# Switch_Decoderv06.net
KiCad netlist of a schematic drawn in EAGLE
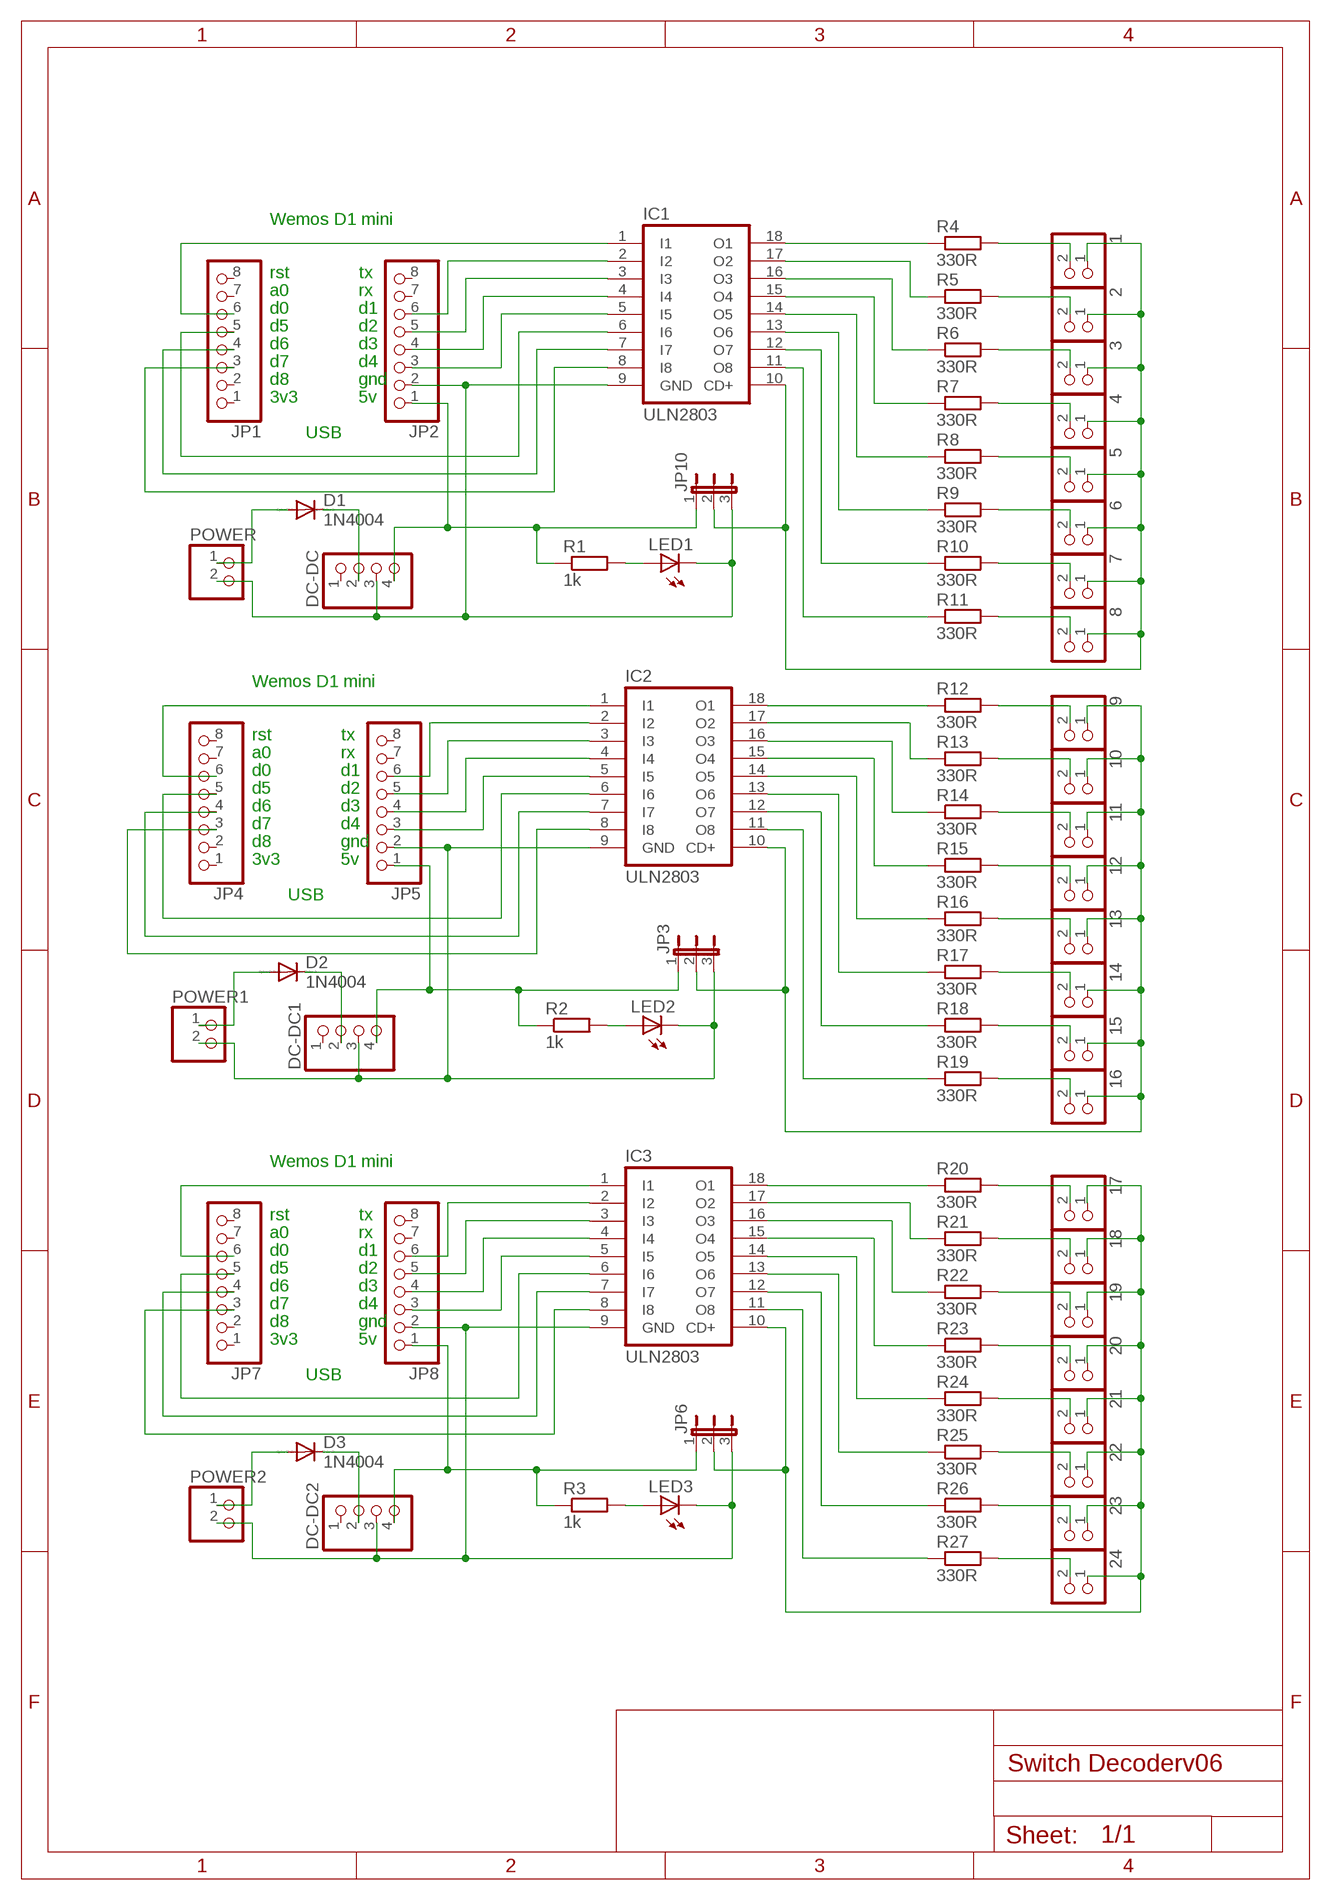
[diagram p0: schematic, sheet 1]

(export (version "E")
  (design (tool "Eeschema 10.0.6"))
  (components
    (comp (ref "1")
      (value "PINHD-1X2")
      (footprint "eagle-import:1X02")
      (libsource (lib "eagle-import") (part "PINHD-1X2"))
    )
    (comp (ref "2")
      (value "PINHD-1X2")
      (footprint "eagle-import:1X02")
      (libsource (lib "eagle-import") (part "PINHD-1X2"))
    )
    (comp (ref "3")
      (value "PINHD-1X2")
      (footprint "eagle-import:1X02")
      (libsource (lib "eagle-import") (part "PINHD-1X2"))
    )
    (comp (ref "4")
      (value "PINHD-1X2")
      (footprint "eagle-import:1X02")
      (libsource (lib "eagle-import") (part "PINHD-1X2"))
    )
    (comp (ref "5")
      (value "PINHD-1X2")
      (footprint "eagle-import:1X02")
      (libsource (lib "eagle-import") (part "PINHD-1X2"))
    )
    (comp (ref "6")
      (value "PINHD-1X2")
      (footprint "eagle-import:1X02")
      (libsource (lib "eagle-import") (part "PINHD-1X2"))
    )
    (comp (ref "7")
      (value "PINHD-1X2")
      (footprint "eagle-import:1X02")
      (libsource (lib "eagle-import") (part "PINHD-1X2"))
    )
    (comp (ref "8")
      (value "PINHD-1X2")
      (footprint "eagle-import:1X02")
      (libsource (lib "eagle-import") (part "PINHD-1X2"))
    )
    (comp (ref "9")
      (value "PINHD-1X2")
      (footprint "eagle-import:1X02")
      (libsource (lib "eagle-import") (part "PINHD-1X2"))
    )
    (comp (ref "10")
      (value "PINHD-1X2")
      (footprint "eagle-import:1X02")
      (libsource (lib "eagle-import") (part "PINHD-1X2"))
    )
    (comp (ref "11")
      (value "PINHD-1X2")
      (footprint "eagle-import:1X02")
      (libsource (lib "eagle-import") (part "PINHD-1X2"))
    )
    (comp (ref "12")
      (value "PINHD-1X2")
      (footprint "eagle-import:1X02")
      (libsource (lib "eagle-import") (part "PINHD-1X2"))
    )
    (comp (ref "13")
      (value "PINHD-1X2")
      (footprint "eagle-import:1X02")
      (libsource (lib "eagle-import") (part "PINHD-1X2"))
    )
    (comp (ref "14")
      (value "PINHD-1X2")
      (footprint "eagle-import:1X02")
      (libsource (lib "eagle-import") (part "PINHD-1X2"))
    )
    (comp (ref "15")
      (value "PINHD-1X2")
      (footprint "eagle-import:1X02")
      (libsource (lib "eagle-import") (part "PINHD-1X2"))
    )
    (comp (ref "16")
      (value "PINHD-1X2")
      (footprint "eagle-import:1X02")
      (libsource (lib "eagle-import") (part "PINHD-1X2"))
    )
    (comp (ref "17")
      (value "PINHD-1X2")
      (footprint "eagle-import:1X02")
      (libsource (lib "eagle-import") (part "PINHD-1X2"))
    )
    (comp (ref "18")
      (value "PINHD-1X2")
      (footprint "eagle-import:1X02")
      (libsource (lib "eagle-import") (part "PINHD-1X2"))
    )
    (comp (ref "19")
      (value "PINHD-1X2")
      (footprint "eagle-import:1X02")
      (libsource (lib "eagle-import") (part "PINHD-1X2"))
    )
    (comp (ref "20")
      (value "PINHD-1X2")
      (footprint "eagle-import:1X02")
      (libsource (lib "eagle-import") (part "PINHD-1X2"))
    )
    (comp (ref "21")
      (value "PINHD-1X2")
      (footprint "eagle-import:1X02")
      (libsource (lib "eagle-import") (part "PINHD-1X2"))
    )
    (comp (ref "22")
      (value "PINHD-1X2")
      (footprint "eagle-import:1X02")
      (libsource (lib "eagle-import") (part "PINHD-1X2"))
    )
    (comp (ref "23")
      (value "PINHD-1X2")
      (footprint "eagle-import:1X02")
      (libsource (lib "eagle-import") (part "PINHD-1X2"))
    )
    (comp (ref "24")
      (value "PINHD-1X2")
      (footprint "eagle-import:1X02")
      (libsource (lib "eagle-import") (part "PINHD-1X2"))
    )
    (comp (ref "D1")
      (value "1N4004")
      (footprint "eagle-import:DO41-10")
      (libsource (lib "eagle-import") (part "1N4004"))
    )
    (comp (ref "D2")
      (value "1N4004")
      (footprint "eagle-import:DO41-10")
      (libsource (lib "eagle-import") (part "1N4004"))
    )
    (comp (ref "D3")
      (value "1N4004")
      (footprint "eagle-import:DO41-10")
      (libsource (lib "eagle-import") (part "1N4004"))
    )
    (comp (ref "DC-DC")
      (value "PINHD-1X4")
      (footprint "eagle-import:1X04")
      (libsource (lib "eagle-import") (part "PINHD-1X4"))
    )
    (comp (ref "DC-DC1")
      (value "PINHD-1X4")
      (footprint "eagle-import:1X04")
      (libsource (lib "eagle-import") (part "PINHD-1X4"))
    )
    (comp (ref "DC-DC2")
      (value "PINHD-1X4")
      (footprint "eagle-import:1X04")
      (libsource (lib "eagle-import") (part "PINHD-1X4"))
    )
    (comp (ref "IC1")
      (value "ULN2803")
      (footprint "eagle-import:DIL18")
      (libsource (lib "eagle-import") (part "ULN2803A"))
    )
    (comp (ref "IC2")
      (value "ULN2803")
      (footprint "eagle-import:DIL18")
      (libsource (lib "eagle-import") (part "ULN2803A"))
    )
    (comp (ref "IC3")
      (value "ULN2803")
      (footprint "eagle-import:DIL18")
      (libsource (lib "eagle-import") (part "ULN2803A"))
    )
    (comp (ref "JP1")
      (value "PINHD-1X8")
      (footprint "eagle-import:1X08")
      (libsource (lib "eagle-import") (part "PINHD-1X8"))
    )
    (comp (ref "JP2")
      (value "PINHD-1X8")
      (footprint "eagle-import:1X08")
      (libsource (lib "eagle-import") (part "PINHD-1X8"))
    )
    (comp (ref "JP3")
      (value "JP2E")
      (footprint "eagle-import:JP2")
      (libsource (lib "eagle-import") (part "JP2E"))
    )
    (comp (ref "JP4")
      (value "PINHD-1X8")
      (footprint "eagle-import:1X08")
      (libsource (lib "eagle-import") (part "PINHD-1X8"))
    )
    (comp (ref "JP5")
      (value "PINHD-1X8")
      (footprint "eagle-import:1X08")
      (libsource (lib "eagle-import") (part "PINHD-1X8"))
    )
    (comp (ref "JP6")
      (value "JP2E")
      (footprint "eagle-import:JP2")
      (libsource (lib "eagle-import") (part "JP2E"))
    )
    (comp (ref "JP7")
      (value "PINHD-1X8")
      (footprint "eagle-import:1X08")
      (libsource (lib "eagle-import") (part "PINHD-1X8"))
    )
    (comp (ref "JP8")
      (value "PINHD-1X8")
      (footprint "eagle-import:1X08")
      (libsource (lib "eagle-import") (part "PINHD-1X8"))
    )
    (comp (ref "JP10")
      (value "JP2E")
      (footprint "eagle-import:JP2")
      (libsource (lib "eagle-import") (part "JP2E"))
    )
    (comp (ref "LED1")
      (value "LED3MM")
      (footprint "eagle-import:LED3MM")
      (libsource (lib "eagle-import") (part "LED3MM"))
    )
    (comp (ref "LED2")
      (value "LED3MM")
      (footprint "eagle-import:LED3MM")
      (libsource (lib "eagle-import") (part "LED3MM"))
    )
    (comp (ref "LED3")
      (value "LED3MM")
      (footprint "eagle-import:LED3MM")
      (libsource (lib "eagle-import") (part "LED3MM"))
    )
    (comp (ref "POWER")
      (value "PINHD-1X2")
      (footprint "eagle-import:1X02")
      (libsource (lib "eagle-import") (part "PINHD-1X2"))
    )
    (comp (ref "POWER1")
      (value "PINHD-1X2")
      (footprint "eagle-import:1X02")
      (libsource (lib "eagle-import") (part "PINHD-1X2"))
    )
    (comp (ref "POWER2")
      (value "PINHD-1X2")
      (footprint "eagle-import:1X02")
      (libsource (lib "eagle-import") (part "PINHD-1X2"))
    )
    (comp (ref "R1")
      (value "1k")
      (footprint "eagle-import:0309_10")
      (libsource (lib "eagle-import") (part "R-EU_0309/10"))
    )
    (comp (ref "R2")
      (value "1k")
      (footprint "eagle-import:0309_10")
      (libsource (lib "eagle-import") (part "R-EU_0309/10"))
    )
    (comp (ref "R3")
      (value "1k")
      (footprint "eagle-import:0309_10")
      (libsource (lib "eagle-import") (part "R-EU_0309/10"))
    )
    (comp (ref "R4")
      (value "330R")
      (footprint "eagle-import:0207_7")
      (libsource (lib "eagle-import") (part "resistor_348_R-EU_0207/7"))
    )
    (comp (ref "R5")
      (value "330R")
      (footprint "eagle-import:0207_7")
      (libsource (lib "eagle-import") (part "resistor_348_R-EU_0207/7"))
    )
    (comp (ref "R6")
      (value "330R")
      (footprint "eagle-import:0207_7")
      (libsource (lib "eagle-import") (part "resistor_348_R-EU_0207/7"))
    )
    (comp (ref "R7")
      (value "330R")
      (footprint "eagle-import:0207_7")
      (libsource (lib "eagle-import") (part "resistor_348_R-EU_0207/7"))
    )
    (comp (ref "R8")
      (value "330R")
      (footprint "eagle-import:0207_7")
      (libsource (lib "eagle-import") (part "resistor_348_R-EU_0207/7"))
    )
    (comp (ref "R9")
      (value "330R")
      (footprint "eagle-import:0207_7")
      (libsource (lib "eagle-import") (part "resistor_348_R-EU_0207/7"))
    )
    (comp (ref "R10")
      (value "330R")
      (footprint "eagle-import:0207_7")
      (libsource (lib "eagle-import") (part "resistor_348_R-EU_0207/7"))
    )
    (comp (ref "R11")
      (value "330R")
      (footprint "eagle-import:0207_7")
      (libsource (lib "eagle-import") (part "resistor_348_R-EU_0207/7"))
    )
    (comp (ref "R12")
      (value "330R")
      (footprint "eagle-import:0207_7")
      (libsource (lib "eagle-import") (part "resistor_348_R-EU_0207/7"))
    )
    (comp (ref "R13")
      (value "330R")
      (footprint "eagle-import:0207_7")
      (libsource (lib "eagle-import") (part "resistor_348_R-EU_0207/7"))
    )
    (comp (ref "R14")
      (value "330R")
      (footprint "eagle-import:0207_7")
      (libsource (lib "eagle-import") (part "resistor_348_R-EU_0207/7"))
    )
    (comp (ref "R15")
      (value "330R")
      (footprint "eagle-import:0207_7")
      (libsource (lib "eagle-import") (part "resistor_348_R-EU_0207/7"))
    )
    (comp (ref "R16")
      (value "330R")
      (footprint "eagle-import:0207_7")
      (libsource (lib "eagle-import") (part "resistor_348_R-EU_0207/7"))
    )
    (comp (ref "R17")
      (value "330R")
      (footprint "eagle-import:0207_7")
      (libsource (lib "eagle-import") (part "resistor_348_R-EU_0207/7"))
    )
    (comp (ref "R18")
      (value "330R")
      (footprint "eagle-import:0207_7")
      (libsource (lib "eagle-import") (part "resistor_348_R-EU_0207/7"))
    )
    (comp (ref "R19")
      (value "330R")
      (footprint "eagle-import:0207_7")
      (libsource (lib "eagle-import") (part "resistor_348_R-EU_0207/7"))
    )
    (comp (ref "R20")
      (value "330R")
      (footprint "eagle-import:0207_7")
      (libsource (lib "eagle-import") (part "resistor_348_R-EU_0207/7"))
    )
    (comp (ref "R21")
      (value "330R")
      (footprint "eagle-import:0207_7")
      (libsource (lib "eagle-import") (part "resistor_348_R-EU_0207/7"))
    )
    (comp (ref "R22")
      (value "330R")
      (footprint "eagle-import:0207_7")
      (libsource (lib "eagle-import") (part "resistor_348_R-EU_0207/7"))
    )
    (comp (ref "R23")
      (value "330R")
      (footprint "eagle-import:0207_7")
      (libsource (lib "eagle-import") (part "resistor_348_R-EU_0207/7"))
    )
    (comp (ref "R24")
      (value "330R")
      (footprint "eagle-import:0207_7")
      (libsource (lib "eagle-import") (part "resistor_348_R-EU_0207/7"))
    )
    (comp (ref "R25")
      (value "330R")
      (footprint "eagle-import:0207_7")
      (libsource (lib "eagle-import") (part "resistor_348_R-EU_0207/7"))
    )
    (comp (ref "R26")
      (value "330R")
      (footprint "eagle-import:0207_7")
      (libsource (lib "eagle-import") (part "resistor_348_R-EU_0207/7"))
    )
    (comp (ref "R27")
      (value "330R")
      (footprint "eagle-import:0207_7")
      (libsource (lib "eagle-import") (part "resistor_348_R-EU_0207/7"))
    )
  )
  (nets
    (net (code "1") (name "Net-(1-Pad2)") (class "Default")
      (node (ref "1") (pin "2") (pinfunction "2_2") (pintype "passive"))
      (node (ref "R4") (pin "2") (pinfunction "2_2") (pintype "passive"))
    )
    (net (code "2") (name "Net-(2-Pad2)") (class "Default")
      (node (ref "2") (pin "2") (pinfunction "2_2") (pintype "passive"))
      (node (ref "R5") (pin "2") (pinfunction "2_2") (pintype "passive"))
    )
    (net (code "3") (name "Net-(3-Pad2)") (class "Default")
      (node (ref "3") (pin "2") (pinfunction "2_2") (pintype "passive"))
      (node (ref "R6") (pin "2") (pinfunction "2_2") (pintype "passive"))
    )
    (net (code "4") (name "Net-(4-Pad2)") (class "Default")
      (node (ref "4") (pin "2") (pinfunction "2_2") (pintype "passive"))
      (node (ref "R7") (pin "2") (pinfunction "2_2") (pintype "passive"))
    )
    (net (code "5") (name "Net-(5-Pad2)") (class "Default")
      (node (ref "5") (pin "2") (pinfunction "2_2") (pintype "passive"))
      (node (ref "R8") (pin "2") (pinfunction "2_2") (pintype "passive"))
    )
    (net (code "6") (name "Net-(6-Pad2)") (class "Default")
      (node (ref "6") (pin "2") (pinfunction "2_2") (pintype "passive"))
      (node (ref "R9") (pin "2") (pinfunction "2_2") (pintype "passive"))
    )
    (net (code "7") (name "Net-(7-Pad2)") (class "Default")
      (node (ref "7") (pin "2") (pinfunction "2_2") (pintype "passive"))
      (node (ref "R10") (pin "2") (pinfunction "2_2") (pintype "passive"))
    )
    (net (code "8") (name "Net-(8-Pad2)") (class "Default")
      (node (ref "8") (pin "2") (pinfunction "2_2") (pintype "passive"))
      (node (ref "R11") (pin "2") (pinfunction "2_2") (pintype "passive"))
    )
    (net (code "9") (name "Net-(9-Pad2)") (class "Default")
      (node (ref "9") (pin "2") (pinfunction "2_2") (pintype "passive"))
      (node (ref "R12") (pin "2") (pinfunction "2_2") (pintype "passive"))
    )
    (net (code "10") (name "Net-(10-Pad2)") (class "Default")
      (node (ref "10") (pin "2") (pinfunction "2_2") (pintype "passive"))
      (node (ref "R13") (pin "2") (pinfunction "2_2") (pintype "passive"))
    )
    (net (code "11") (name "Net-(11-Pad2)") (class "Default")
      (node (ref "11") (pin "2") (pinfunction "2_2") (pintype "passive"))
      (node (ref "R14") (pin "2") (pinfunction "2_2") (pintype "passive"))
    )
    (net (code "12") (name "Net-(12-Pad2)") (class "Default")
      (node (ref "12") (pin "2") (pinfunction "2_2") (pintype "passive"))
      (node (ref "R15") (pin "2") (pinfunction "2_2") (pintype "passive"))
    )
    (net (code "13") (name "Net-(13-Pad2)") (class "Default")
      (node (ref "13") (pin "2") (pinfunction "2_2") (pintype "passive"))
      (node (ref "R16") (pin "2") (pinfunction "2_2") (pintype "passive"))
    )
    (net (code "14") (name "Net-(14-Pad2)") (class "Default")
      (node (ref "14") (pin "2") (pinfunction "2_2") (pintype "passive"))
      (node (ref "R17") (pin "2") (pinfunction "2_2") (pintype "passive"))
    )
    (net (code "15") (name "Net-(15-Pad2)") (class "Default")
      (node (ref "15") (pin "2") (pinfunction "2_2") (pintype "passive"))
      (node (ref "R18") (pin "2") (pinfunction "2_2") (pintype "passive"))
    )
    (net (code "16") (name "Net-(16-Pad2)") (class "Default")
      (node (ref "16") (pin "2") (pinfunction "2_2") (pintype "passive"))
      (node (ref "R19") (pin "2") (pinfunction "2_2") (pintype "passive"))
    )
    (net (code "17") (name "Net-(17-Pad2)") (class "Default")
      (node (ref "17") (pin "2") (pinfunction "2_2") (pintype "passive"))
      (node (ref "R20") (pin "2") (pinfunction "2_2") (pintype "passive"))
    )
    (net (code "18") (name "Net-(18-Pad2)") (class "Default")
      (node (ref "18") (pin "2") (pinfunction "2_2") (pintype "passive"))
      (node (ref "R21") (pin "2") (pinfunction "2_2") (pintype "passive"))
    )
    (net (code "19") (name "Net-(19-Pad2)") (class "Default")
      (node (ref "19") (pin "2") (pinfunction "2_2") (pintype "passive"))
      (node (ref "R22") (pin "2") (pinfunction "2_2") (pintype "passive"))
    )
    (net (code "20") (name "Net-(20-Pad2)") (class "Default")
      (node (ref "20") (pin "2") (pinfunction "2_2") (pintype "passive"))
      (node (ref "R23") (pin "2") (pinfunction "2_2") (pintype "passive"))
    )
    (net (code "21") (name "Net-(21-Pad2)") (class "Default")
      (node (ref "21") (pin "2") (pinfunction "2_2") (pintype "passive"))
      (node (ref "R24") (pin "2") (pinfunction "2_2") (pintype "passive"))
    )
    (net (code "22") (name "Net-(22-Pad2)") (class "Default")
      (node (ref "22") (pin "2") (pinfunction "2_2") (pintype "passive"))
      (node (ref "R25") (pin "2") (pinfunction "2_2") (pintype "passive"))
    )
    (net (code "23") (name "Net-(23-Pad2)") (class "Default")
      (node (ref "23") (pin "2") (pinfunction "2_2") (pintype "passive"))
      (node (ref "R26") (pin "2") (pinfunction "2_2") (pintype "passive"))
    )
    (net (code "24") (name "Net-(24-Pad2)") (class "Default")
      (node (ref "24") (pin "2") (pinfunction "2_2") (pintype "passive"))
      (node (ref "R27") (pin "2") (pinfunction "2_2") (pintype "passive"))
    )
    (net (code "25") (name "Net-(D1-PadA)") (class "Default")
      (node (ref "D1") (pin "A") (pinfunction "A_A") (pintype "passive"))
      (node (ref "POWER") (pin "1") (pinfunction "1_1") (pintype "passive"))
    )
    (net (code "26") (name "Net-(D1-PadC)") (class "Default")
      (node (ref "D1") (pin "C") (pinfunction "C_C") (pintype "passive"))
      (node (ref "DC-DC") (pin "2") (pinfunction "2_2") (pintype "passive"))
    )
    (net (code "27") (name "Net-(D2-PadA)") (class "Default")
      (node (ref "D2") (pin "A") (pinfunction "A_A") (pintype "passive"))
      (node (ref "POWER1") (pin "1") (pinfunction "1_1") (pintype "passive"))
    )
    (net (code "28") (name "Net-(D2-PadC)") (class "Default")
      (node (ref "D2") (pin "C") (pinfunction "C_C") (pintype "passive"))
      (node (ref "DC-DC1") (pin "2") (pinfunction "2_2") (pintype "passive"))
    )
    (net (code "29") (name "Net-(D3-PadA)") (class "Default")
      (node (ref "D3") (pin "A") (pinfunction "A_A") (pintype "passive"))
      (node (ref "POWER2") (pin "1") (pinfunction "1_1") (pintype "passive"))
    )
    (net (code "30") (name "Net-(D3-PadC)") (class "Default")
      (node (ref "D3") (pin "C") (pinfunction "C_C") (pintype "passive"))
      (node (ref "DC-DC2") (pin "2") (pinfunction "2_2") (pintype "passive"))
    )
    (net (code "31") (name "Net-(DC-DC-Pad4)") (class "Default")
      (node (ref "DC-DC") (pin "4") (pinfunction "4_4") (pintype "passive"))
      (node (ref "JP10") (pin "1") (pinfunction "1_1") (pintype "passive"))
      (node (ref "JP2") (pin "1") (pinfunction "1_1") (pintype "passive"))
      (node (ref "R1") (pin "1") (pinfunction "1_1") (pintype "passive"))
    )
    (net (code "32") (name "Net-(DC-DC1-Pad4)") (class "Default")
      (node (ref "DC-DC1") (pin "4") (pinfunction "4_4") (pintype "passive"))
      (node (ref "JP3") (pin "1") (pinfunction "1_1") (pintype "passive"))
      (node (ref "JP5") (pin "1") (pinfunction "1_1") (pintype "passive"))
      (node (ref "R2") (pin "1") (pinfunction "1_1") (pintype "passive"))
    )
    (net (code "33") (name "Net-(DC-DC2-Pad4)") (class "Default")
      (node (ref "DC-DC2") (pin "4") (pinfunction "4_4") (pintype "passive"))
      (node (ref "JP6") (pin "1") (pinfunction "1_1") (pintype "passive"))
      (node (ref "JP8") (pin "1") (pinfunction "1_1") (pintype "passive"))
      (node (ref "R3") (pin "1") (pinfunction "1_1") (pintype "passive"))
    )
    (net (code "34") (name "Net-(IC1-CD+)") (class "Default")
      (node (ref "1") (pin "1") (pinfunction "1_1") (pintype "passive"))
      (node (ref "2") (pin "1") (pinfunction "1_1") (pintype "passive"))
      (node (ref "3") (pin "1") (pinfunction "1_1") (pintype "passive"))
      (node (ref "4") (pin "1") (pinfunction "1_1") (pintype "passive"))
      (node (ref "5") (pin "1") (pinfunction "1_1") (pintype "passive"))
      (node (ref "6") (pin "1") (pinfunction "1_1") (pintype "passive"))
      (node (ref "7") (pin "1") (pinfunction "1_1") (pintype "passive"))
      (node (ref "8") (pin "1") (pinfunction "1_1") (pintype "passive"))
      (node (ref "IC1") (pin "10") (pinfunction "CD+_10") (pintype "passive"))
      (node (ref "JP10") (pin "2") (pinfunction "2_2") (pintype "passive"))
    )
    (net (code "35") (name "Net-(IC1-GND)") (class "Default")
      (node (ref "DC-DC") (pin "3") (pinfunction "3_3") (pintype "passive"))
      (node (ref "IC1") (pin "9") (pinfunction "GND_9") (pintype "power_in"))
      (node (ref "JP10") (pin "3") (pinfunction "3_3") (pintype "passive"))
      (node (ref "JP2") (pin "2") (pinfunction "2_2") (pintype "passive"))
      (node (ref "LED1") (pin "K") (pinfunction "C_K") (pintype "passive"))
      (node (ref "POWER") (pin "2") (pinfunction "2_2") (pintype "passive"))
    )
    (net (code "36") (name "Net-(IC1-I1)") (class "Default")
      (node (ref "IC1") (pin "1") (pinfunction "I1_1") (pintype "input"))
      (node (ref "JP1") (pin "6") (pinfunction "6_6") (pintype "passive"))
    )
    (net (code "37") (name "Net-(IC1-I2)") (class "Default")
      (node (ref "IC1") (pin "2") (pinfunction "I2_2") (pintype "input"))
      (node (ref "JP2") (pin "6") (pinfunction "6_6") (pintype "passive"))
    )
    (net (code "38") (name "Net-(IC1-I3)") (class "Default")
      (node (ref "IC1") (pin "3") (pinfunction "I3_3") (pintype "input"))
      (node (ref "JP2") (pin "5") (pinfunction "5_5") (pintype "passive"))
    )
    (net (code "39") (name "Net-(IC1-I4)") (class "Default")
      (node (ref "IC1") (pin "4") (pinfunction "I4_4") (pintype "input"))
      (node (ref "JP2") (pin "4") (pinfunction "4_4") (pintype "passive"))
    )
    (net (code "40") (name "Net-(IC1-I5)") (class "Default")
      (node (ref "IC1") (pin "5") (pinfunction "I5_5") (pintype "input"))
      (node (ref "JP2") (pin "3") (pinfunction "3_3") (pintype "passive"))
    )
    (net (code "41") (name "Net-(IC1-I6)") (class "Default")
      (node (ref "IC1") (pin "6") (pinfunction "I6_6") (pintype "input"))
      (node (ref "JP1") (pin "5") (pinfunction "5_5") (pintype "passive"))
    )
    (net (code "42") (name "Net-(IC1-I7)") (class "Default")
      (node (ref "IC1") (pin "7") (pinfunction "I7_7") (pintype "input"))
      (node (ref "JP1") (pin "4") (pinfunction "4_4") (pintype "passive"))
    )
    (net (code "43") (name "Net-(IC1-I8)") (class "Default")
      (node (ref "IC1") (pin "8") (pinfunction "I8_8") (pintype "input"))
      (node (ref "JP1") (pin "3") (pinfunction "3_3") (pintype "passive"))
    )
    (net (code "44") (name "Net-(IC1-O1)") (class "Default")
      (node (ref "IC1") (pin "18") (pinfunction "O1_18") (pintype "open_collector"))
      (node (ref "R4") (pin "1") (pinfunction "1_1") (pintype "passive"))
    )
    (net (code "45") (name "Net-(IC1-O2)") (class "Default")
      (node (ref "IC1") (pin "17") (pinfunction "O2_17") (pintype "open_collector"))
      (node (ref "R5") (pin "1") (pinfunction "1_1") (pintype "passive"))
    )
    (net (code "46") (name "Net-(IC1-O3)") (class "Default")
      (node (ref "IC1") (pin "16") (pinfunction "O3_16") (pintype "open_collector"))
      (node (ref "R6") (pin "1") (pinfunction "1_1") (pintype "passive"))
    )
    (net (code "47") (name "Net-(IC1-O4)") (class "Default")
      (node (ref "IC1") (pin "15") (pinfunction "O4_15") (pintype "open_collector"))
      (node (ref "R7") (pin "1") (pinfunction "1_1") (pintype "passive"))
    )
    (net (code "48") (name "Net-(IC1-O5)") (class "Default")
      (node (ref "IC1") (pin "14") (pinfunction "O5_14") (pintype "open_collector"))
      (node (ref "R8") (pin "1") (pinfunction "1_1") (pintype "passive"))
    )
    (net (code "49") (name "Net-(IC1-O6)") (class "Default")
      (node (ref "IC1") (pin "13") (pinfunction "O6_13") (pintype "open_collector"))
      (node (ref "R9") (pin "1") (pinfunction "1_1") (pintype "passive"))
    )
    (net (code "50") (name "Net-(IC1-O7)") (class "Default")
      (node (ref "IC1") (pin "12") (pinfunction "O7_12") (pintype "open_collector"))
      (node (ref "R10") (pin "1") (pinfunction "1_1") (pintype "passive"))
    )
    (net (code "51") (name "Net-(IC1-O8)") (class "Default")
      (node (ref "IC1") (pin "11") (pinfunction "O8_11") (pintype "open_collector"))
      (node (ref "R11") (pin "1") (pinfunction "1_1") (pintype "passive"))
    )
    (net (code "52") (name "Net-(IC2-CD+)") (class "Default")
      (node (ref "10") (pin "1") (pinfunction "1_1") (pintype "passive"))
      (node (ref "11") (pin "1") (pinfunction "1_1") (pintype "passive"))
      (node (ref "12") (pin "1") (pinfunction "1_1") (pintype "passive"))
      (node (ref "13") (pin "1") (pinfunction "1_1") (pintype "passive"))
      (node (ref "14") (pin "1") (pinfunction "1_1") (pintype "passive"))
      (node (ref "15") (pin "1") (pinfunction "1_1") (pintype "passive"))
      (node (ref "16") (pin "1") (pinfunction "1_1") (pintype "passive"))
      (node (ref "9") (pin "1") (pinfunction "1_1") (pintype "passive"))
      (node (ref "IC2") (pin "10") (pinfunction "CD+_10") (pintype "passive"))
      (node (ref "JP3") (pin "2") (pinfunction "2_2") (pintype "passive"))
    )
    (net (code "53") (name "Net-(IC2-GND)") (class "Default")
      (node (ref "DC-DC1") (pin "3") (pinfunction "3_3") (pintype "passive"))
      (node (ref "IC2") (pin "9") (pinfunction "GND_9") (pintype "power_in"))
      (node (ref "JP3") (pin "3") (pinfunction "3_3") (pintype "passive"))
      (node (ref "JP5") (pin "2") (pinfunction "2_2") (pintype "passive"))
      (node (ref "LED2") (pin "K") (pinfunction "C_K") (pintype "passive"))
      (node (ref "POWER1") (pin "2") (pinfunction "2_2") (pintype "passive"))
    )
    (net (code "54") (name "Net-(IC2-I1)") (class "Default")
      (node (ref "IC2") (pin "1") (pinfunction "I1_1") (pintype "input"))
      (node (ref "JP4") (pin "6") (pinfunction "6_6") (pintype "passive"))
    )
    (net (code "55") (name "Net-(IC2-I2)") (class "Default")
      (node (ref "IC2") (pin "2") (pinfunction "I2_2") (pintype "input"))
      (node (ref "JP5") (pin "6") (pinfunction "6_6") (pintype "passive"))
    )
    (net (code "56") (name "Net-(IC2-I3)") (class "Default")
      (node (ref "IC2") (pin "3") (pinfunction "I3_3") (pintype "input"))
      (node (ref "JP5") (pin "5") (pinfunction "5_5") (pintype "passive"))
    )
    (net (code "57") (name "Net-(IC2-I4)") (class "Default")
      (node (ref "IC2") (pin "4") (pinfunction "I4_4") (pintype "input"))
      (node (ref "JP5") (pin "4") (pinfunction "4_4") (pintype "passive"))
    )
    (net (code "58") (name "Net-(IC2-I5)") (class "Default")
      (node (ref "IC2") (pin "5") (pinfunction "I5_5") (pintype "input"))
      (node (ref "JP5") (pin "3") (pinfunction "3_3") (pintype "passive"))
    )
    (net (code "59") (name "Net-(IC2-I6)") (class "Default")
      (node (ref "IC2") (pin "6") (pinfunction "I6_6") (pintype "input"))
      (node (ref "JP4") (pin "5") (pinfunction "5_5") (pintype "passive"))
    )
    (net (code "60") (name "Net-(IC2-I7)") (class "Default")
      (node (ref "IC2") (pin "7") (pinfunction "I7_7") (pintype "input"))
      (node (ref "JP4") (pin "4") (pinfunction "4_4") (pintype "passive"))
    )
    (net (code "61") (name "Net-(IC2-I8)") (class "Default")
      (node (ref "IC2") (pin "8") (pinfunction "I8_8") (pintype "input"))
      (node (ref "JP4") (pin "3") (pinfunction "3_3") (pintype "passive"))
    )
    (net (code "62") (name "Net-(IC2-O1)") (class "Default")
      (node (ref "IC2") (pin "18") (pinfunction "O1_18") (pintype "open_collector"))
      (node (ref "R12") (pin "1") (pinfunction "1_1") (pintype "passive"))
    )
    (net (code "63") (name "Net-(IC2-O2)") (class "Default")
      (node (ref "IC2") (pin "17") (pinfunction "O2_17") (pintype "open_collector"))
      (node (ref "R13") (pin "1") (pinfunction "1_1") (pintype "passive"))
    )
    (net (code "64") (name "Net-(IC2-O3)") (class "Default")
      (node (ref "IC2") (pin "16") (pinfunction "O3_16") (pintype "open_collector"))
      (node (ref "R14") (pin "1") (pinfunction "1_1") (pintype "passive"))
    )
    (net (code "65") (name "Net-(IC2-O4)") (class "Default")
      (node (ref "IC2") (pin "15") (pinfunction "O4_15") (pintype "open_collector"))
      (node (ref "R15") (pin "1") (pinfunction "1_1") (pintype "passive"))
    )
    (net (code "66") (name "Net-(IC2-O5)") (class "Default")
      (node (ref "IC2") (pin "14") (pinfunction "O5_14") (pintype "open_collector"))
      (node (ref "R16") (pin "1") (pinfunction "1_1") (pintype "passive"))
    )
    (net (code "67") (name "Net-(IC2-O6)") (class "Default")
      (node (ref "IC2") (pin "13") (pinfunction "O6_13") (pintype "open_collector"))
      (node (ref "R17") (pin "1") (pinfunction "1_1") (pintype "passive"))
    )
    (net (code "68") (name "Net-(IC2-O7)") (class "Default")
      (node (ref "IC2") (pin "12") (pinfunction "O7_12") (pintype "open_collector"))
      (node (ref "R18") (pin "1") (pinfunction "1_1") (pintype "passive"))
    )
    (net (code "69") (name "Net-(IC2-O8)") (class "Default")
      (node (ref "IC2") (pin "11") (pinfunction "O8_11") (pintype "open_collector"))
      (node (ref "R19") (pin "1") (pinfunction "1_1") (pintype "passive"))
    )
    (net (code "70") (name "Net-(IC3-CD+)") (class "Default")
      (node (ref "17") (pin "1") (pinfunction "1_1") (pintype "passive"))
      (node (ref "18") (pin "1") (pinfunction "1_1") (pintype "passive"))
      (node (ref "19") (pin "1") (pinfunction "1_1") (pintype "passive"))
      (node (ref "20") (pin "1") (pinfunction "1_1") (pintype "passive"))
      (node (ref "21") (pin "1") (pinfunction "1_1") (pintype "passive"))
      (node (ref "22") (pin "1") (pinfunction "1_1") (pintype "passive"))
      (node (ref "23") (pin "1") (pinfunction "1_1") (pintype "passive"))
      (node (ref "24") (pin "1") (pinfunction "1_1") (pintype "passive"))
      (node (ref "IC3") (pin "10") (pinfunction "CD+_10") (pintype "passive"))
      (node (ref "JP6") (pin "2") (pinfunction "2_2") (pintype "passive"))
    )
    (net (code "71") (name "Net-(IC3-GND)") (class "Default")
      (node (ref "DC-DC2") (pin "3") (pinfunction "3_3") (pintype "passive"))
      (node (ref "IC3") (pin "9") (pinfunction "GND_9") (pintype "power_in"))
      (node (ref "JP6") (pin "3") (pinfunction "3_3") (pintype "passive"))
      (node (ref "JP8") (pin "2") (pinfunction "2_2") (pintype "passive"))
      (node (ref "LED3") (pin "K") (pinfunction "C_K") (pintype "passive"))
      (node (ref "POWER2") (pin "2") (pinfunction "2_2") (pintype "passive"))
    )
    (net (code "72") (name "Net-(IC3-I1)") (class "Default")
      (node (ref "IC3") (pin "1") (pinfunction "I1_1") (pintype "input"))
      (node (ref "JP7") (pin "6") (pinfunction "6_6") (pintype "passive"))
    )
    (net (code "73") (name "Net-(IC3-I2)") (class "Default")
      (node (ref "IC3") (pin "2") (pinfunction "I2_2") (pintype "input"))
      (node (ref "JP8") (pin "6") (pinfunction "6_6") (pintype "passive"))
    )
    (net (code "74") (name "Net-(IC3-I3)") (class "Default")
      (node (ref "IC3") (pin "3") (pinfunction "I3_3") (pintype "input"))
      (node (ref "JP8") (pin "5") (pinfunction "5_5") (pintype "passive"))
    )
    (net (code "75") (name "Net-(IC3-I4)") (class "Default")
      (node (ref "IC3") (pin "4") (pinfunction "I4_4") (pintype "input"))
      (node (ref "JP8") (pin "4") (pinfunction "4_4") (pintype "passive"))
    )
    (net (code "76") (name "Net-(IC3-I5)") (class "Default")
      (node (ref "IC3") (pin "5") (pinfunction "I5_5") (pintype "input"))
      (node (ref "JP8") (pin "3") (pinfunction "3_3") (pintype "passive"))
    )
    (net (code "77") (name "Net-(IC3-I6)") (class "Default")
      (node (ref "IC3") (pin "6") (pinfunction "I6_6") (pintype "input"))
      (node (ref "JP7") (pin "5") (pinfunction "5_5") (pintype "passive"))
    )
    (net (code "78") (name "Net-(IC3-I7)") (class "Default")
      (node (ref "IC3") (pin "7") (pinfunction "I7_7") (pintype "input"))
      (node (ref "JP7") (pin "4") (pinfunction "4_4") (pintype "passive"))
    )
    (net (code "79") (name "Net-(IC3-I8)") (class "Default")
      (node (ref "IC3") (pin "8") (pinfunction "I8_8") (pintype "input"))
      (node (ref "JP7") (pin "3") (pinfunction "3_3") (pintype "passive"))
    )
    (net (code "80") (name "Net-(IC3-O1)") (class "Default")
      (node (ref "IC3") (pin "18") (pinfunction "O1_18") (pintype "open_collector"))
      (node (ref "R20") (pin "1") (pinfunction "1_1") (pintype "passive"))
    )
    (net (code "81") (name "Net-(IC3-O2)") (class "Default")
      (node (ref "IC3") (pin "17") (pinfunction "O2_17") (pintype "open_collector"))
      (node (ref "R21") (pin "1") (pinfunction "1_1") (pintype "passive"))
    )
    (net (code "82") (name "Net-(IC3-O3)") (class "Default")
      (node (ref "IC3") (pin "16") (pinfunction "O3_16") (pintype "open_collector"))
      (node (ref "R22") (pin "1") (pinfunction "1_1") (pintype "passive"))
    )
    (net (code "83") (name "Net-(IC3-O4)") (class "Default")
      (node (ref "IC3") (pin "15") (pinfunction "O4_15") (pintype "open_collector"))
      (node (ref "R23") (pin "1") (pinfunction "1_1") (pintype "passive"))
    )
    (net (code "84") (name "Net-(IC3-O5)") (class "Default")
      (node (ref "IC3") (pin "14") (pinfunction "O5_14") (pintype "open_collector"))
      (node (ref "R24") (pin "1") (pinfunction "1_1") (pintype "passive"))
    )
    (net (code "85") (name "Net-(IC3-O6)") (class "Default")
      (node (ref "IC3") (pin "13") (pinfunction "O6_13") (pintype "open_collector"))
      (node (ref "R25") (pin "1") (pinfunction "1_1") (pintype "passive"))
    )
    (net (code "86") (name "Net-(IC3-O7)") (class "Default")
      (node (ref "IC3") (pin "12") (pinfunction "O7_12") (pintype "open_collector"))
      (node (ref "R26") (pin "1") (pinfunction "1_1") (pintype "passive"))
    )
    (net (code "87") (name "Net-(IC3-O8)") (class "Default")
      (node (ref "IC3") (pin "11") (pinfunction "O8_11") (pintype "open_collector"))
      (node (ref "R27") (pin "1") (pinfunction "1_1") (pintype "passive"))
    )
    (net (code "88") (name "Net-(LED1-PadA)") (class "Default")
      (node (ref "LED1") (pin "A") (pinfunction "A_A") (pintype "passive"))
      (node (ref "R1") (pin "2") (pinfunction "2_2") (pintype "passive"))
    )
    (net (code "89") (name "Net-(LED2-PadA)") (class "Default")
      (node (ref "LED2") (pin "A") (pinfunction "A_A") (pintype "passive"))
      (node (ref "R2") (pin "2") (pinfunction "2_2") (pintype "passive"))
    )
    (net (code "90") (name "Net-(LED3-PadA)") (class "Default")
      (node (ref "LED3") (pin "A") (pinfunction "A_A") (pintype "passive"))
      (node (ref "R3") (pin "2") (pinfunction "2_2") (pintype "passive"))
    )
    (net (code "91") (name "unconnected-(DC-DC-Pad1)") (class "Default")
      (node (ref "DC-DC") (pin "1") (pinfunction "1_1") (pintype "passive"))
    )
    (net (code "92") (name "unconnected-(DC-DC1-Pad1)") (class "Default")
      (node (ref "DC-DC1") (pin "1") (pinfunction "1_1") (pintype "passive"))
    )
    (net (code "93") (name "unconnected-(DC-DC2-Pad1)") (class "Default")
      (node (ref "DC-DC2") (pin "1") (pinfunction "1_1") (pintype "passive"))
    )
    (net (code "94") (name "unconnected-(JP1-Pad1)") (class "Default")
      (node (ref "JP1") (pin "1") (pinfunction "1_1") (pintype "passive"))
    )
    (net (code "95") (name "unconnected-(JP1-Pad2)") (class "Default")
      (node (ref "JP1") (pin "2") (pinfunction "2_2") (pintype "passive"))
    )
    (net (code "96") (name "unconnected-(JP1-Pad7)") (class "Default")
      (node (ref "JP1") (pin "7") (pinfunction "7_7") (pintype "passive"))
    )
    (net (code "97") (name "unconnected-(JP1-Pad8)") (class "Default")
      (node (ref "JP1") (pin "8") (pinfunction "8_8") (pintype "passive"))
    )
    (net (code "98") (name "unconnected-(JP2-Pad7)") (class "Default")
      (node (ref "JP2") (pin "7") (pinfunction "7_7") (pintype "passive"))
    )
    (net (code "99") (name "unconnected-(JP2-Pad8)") (class "Default")
      (node (ref "JP2") (pin "8") (pinfunction "8_8") (pintype "passive"))
    )
    (net (code "100") (name "unconnected-(JP4-Pad1)") (class "Default")
      (node (ref "JP4") (pin "1") (pinfunction "1_1") (pintype "passive"))
    )
    (net (code "101") (name "unconnected-(JP4-Pad2)") (class "Default")
      (node (ref "JP4") (pin "2") (pinfunction "2_2") (pintype "passive"))
    )
    (net (code "102") (name "unconnected-(JP4-Pad7)") (class "Default")
      (node (ref "JP4") (pin "7") (pinfunction "7_7") (pintype "passive"))
    )
    (net (code "103") (name "unconnected-(JP4-Pad8)") (class "Default")
      (node (ref "JP4") (pin "8") (pinfunction "8_8") (pintype "passive"))
    )
    (net (code "104") (name "unconnected-(JP5-Pad7)") (class "Default")
      (node (ref "JP5") (pin "7") (pinfunction "7_7") (pintype "passive"))
    )
    (net (code "105") (name "unconnected-(JP5-Pad8)") (class "Default")
      (node (ref "JP5") (pin "8") (pinfunction "8_8") (pintype "passive"))
    )
    (net (code "106") (name "unconnected-(JP7-Pad1)") (class "Default")
      (node (ref "JP7") (pin "1") (pinfunction "1_1") (pintype "passive"))
    )
    (net (code "107") (name "unconnected-(JP7-Pad2)") (class "Default")
      (node (ref "JP7") (pin "2") (pinfunction "2_2") (pintype "passive"))
    )
    (net (code "108") (name "unconnected-(JP7-Pad7)") (class "Default")
      (node (ref "JP7") (pin "7") (pinfunction "7_7") (pintype "passive"))
    )
    (net (code "109") (name "unconnected-(JP7-Pad8)") (class "Default")
      (node (ref "JP7") (pin "8") (pinfunction "8_8") (pintype "passive"))
    )
    (net (code "110") (name "unconnected-(JP8-Pad7)") (class "Default")
      (node (ref "JP8") (pin "7") (pinfunction "7_7") (pintype "passive"))
    )
    (net (code "111") (name "unconnected-(JP8-Pad8)") (class "Default")
      (node (ref "JP8") (pin "8") (pinfunction "8_8") (pintype "passive"))
    )
  )
)
